# slimme_meter3.net
KiCad netlist of a schematic drawn in EAGLE
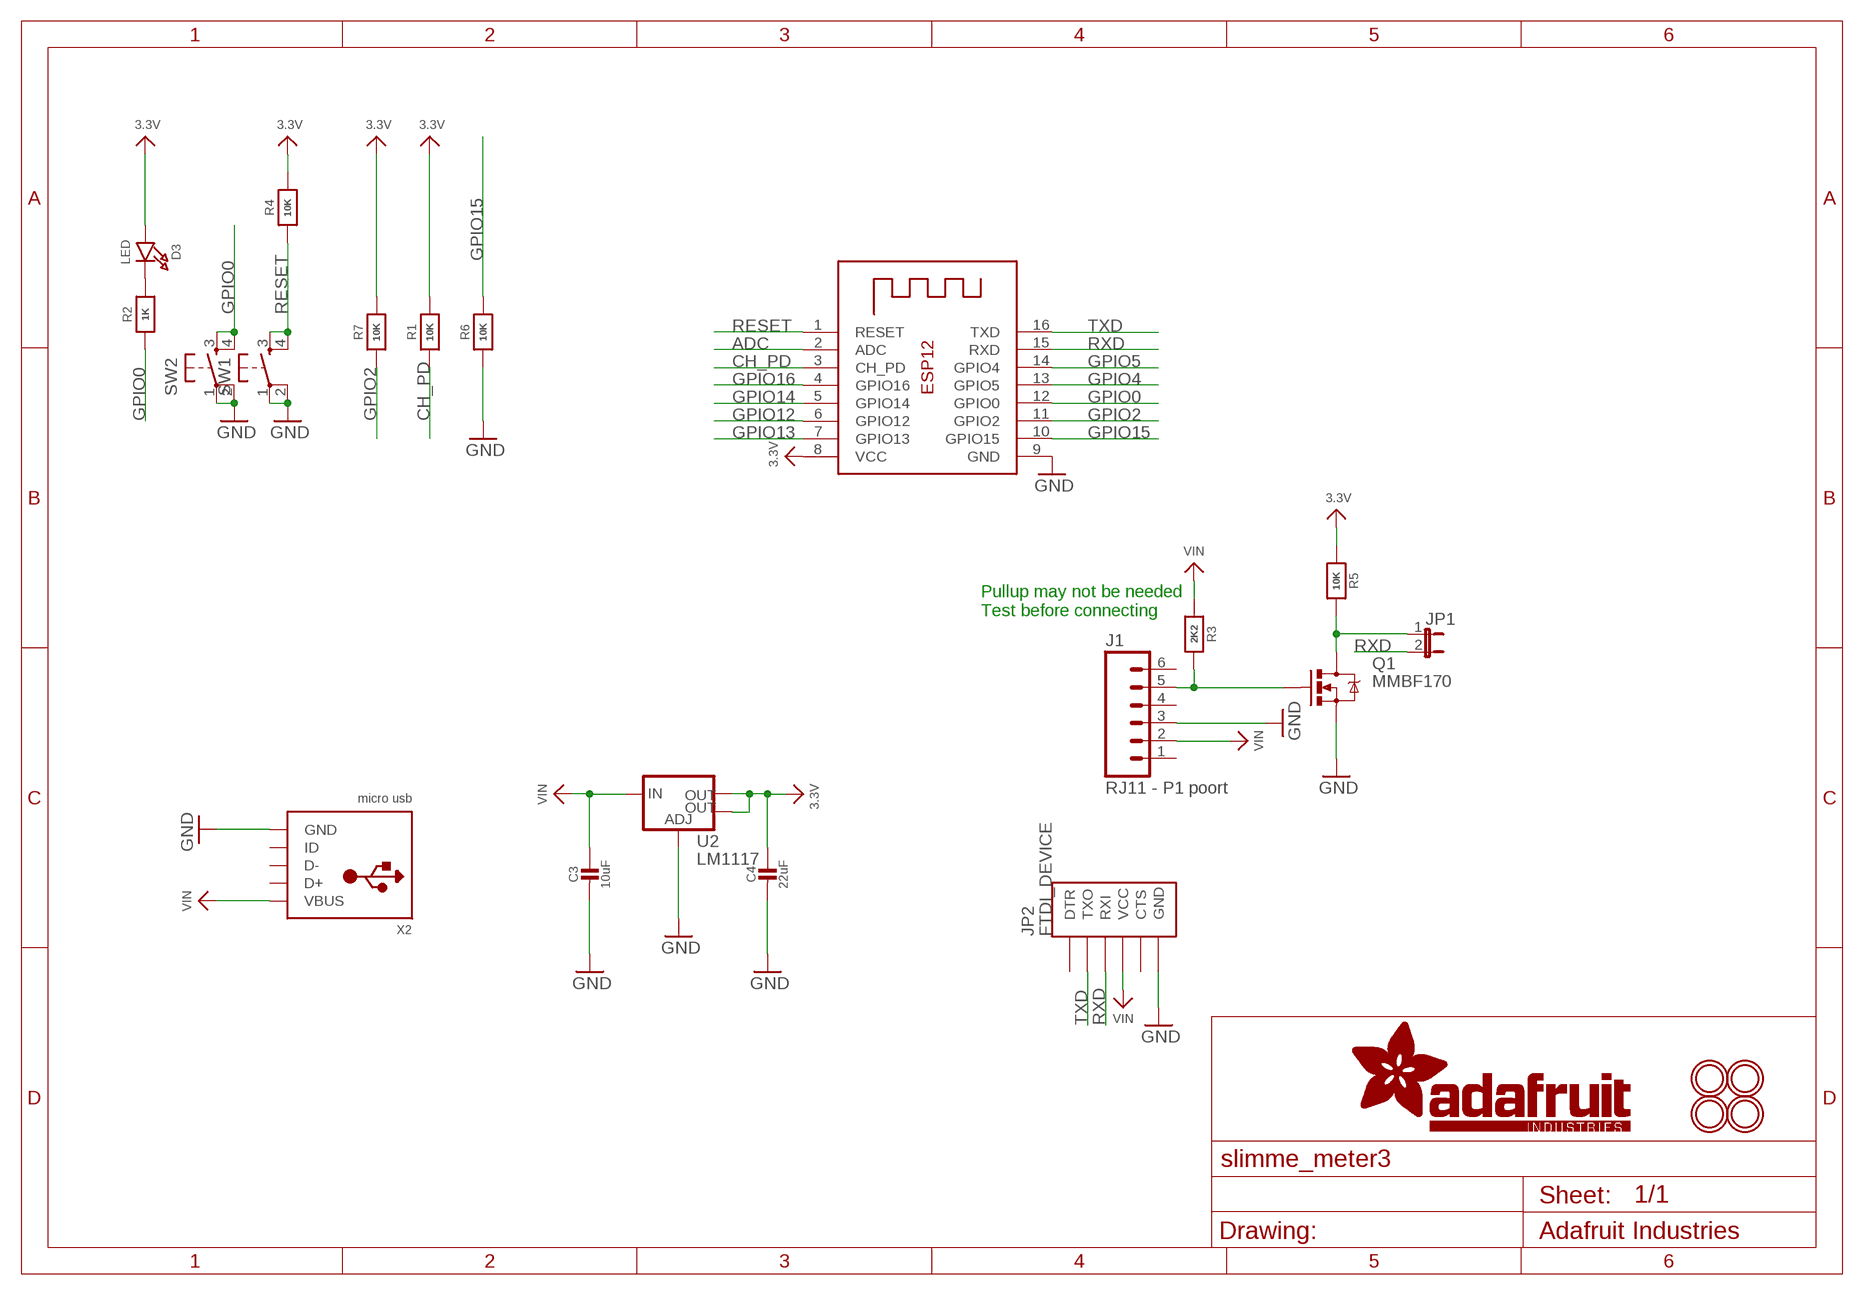
[diagram p0: schematic, sheet 1]

(export (version "E")
  (design (tool "Eeschema 10.0.6"))
  (components
    (comp (ref "C3")
      (value "10uF")
      (footprint "eagle-import:0805-NO")
      (libsource (lib "eagle-import") (part "CAP_CERAMIC0805-NOOUTLINE"))
    )
    (comp (ref "C4")
      (value "22uF")
      (footprint "eagle-import:0805-NO")
      (libsource (lib "eagle-import") (part "CAP_CERAMIC0805-NOOUTLINE"))
    )
    (comp (ref "D3")
      (value "LED")
      (footprint "eagle-import:CHIPLED_0805_NOOUTLINE")
      (libsource (lib "eagle-import") (part "LED0805_NOOUTLINE"))
    )
    (comp (ref "J1")
      (value "RJ11 - P1 poort")
      (footprint "eagle-import:RJ11-6")
      (libsource (lib "eagle-import") (part "RJ11-6PTH"))
    )
    (comp (ref "JP1")
      (value "JUMPER-2PTH")
      (footprint "eagle-import:1X02")
      (libsource (lib "eagle-import") (part "JUMPER-2PTH"))
    )
    (comp (ref "JP2")
      (value "FTDI_DEVICE")
      (footprint "eagle-import:FTDI_DEVICE_SIDE")
      (libsource (lib "eagle-import") (part "FTDI_DEVICE"))
    )
    (comp (ref "Q1")
      (value "MMBF170")
      (footprint "eagle-import:SOT323")
      (libsource (lib "eagle-import") (part "MOSFET-NCHANNEL2N7002PW"))
    )
    (comp (ref "R1")
      (value "10K")
      (footprint "eagle-import:0805-NO")
      (libsource (lib "eagle-import") (part "RESISTOR0805_NOOUTLINE"))
    )
    (comp (ref "R2")
      (value "1K")
      (footprint "eagle-import:0805-NO")
      (libsource (lib "eagle-import") (part "RESISTOR0805_NOOUTLINE"))
    )
    (comp (ref "R3")
      (value "2K2")
      (footprint "eagle-import:0805-NO")
      (libsource (lib "eagle-import") (part "RESISTOR0805_NOOUTLINE"))
    )
    (comp (ref "R4")
      (value "10K")
      (footprint "eagle-import:0805-NO")
      (libsource (lib "eagle-import") (part "RESISTOR0805_NOOUTLINE"))
    )
    (comp (ref "R5")
      (value "10K")
      (footprint "eagle-import:0805-NO")
      (libsource (lib "eagle-import") (part "RESISTOR0805_NOOUTLINE"))
    )
    (comp (ref "R6")
      (value "10K")
      (footprint "eagle-import:0805-NO")
      (libsource (lib "eagle-import") (part "RESISTOR0805_NOOUTLINE"))
    )
    (comp (ref "R7")
      (value "10K")
      (footprint "eagle-import:0805-NO")
      (libsource (lib "eagle-import") (part "RESISTOR0805_NOOUTLINE"))
    )
    (comp (ref "SW1")
      (value "TACTILE-SWITCH-PTH")
      (footprint "eagle-import:TAC-SWITCH-PTH")
      (libsource (lib "eagle-import") (part "TACTILE-SWITCH-PTH"))
    )
    (comp (ref "SW2")
      (value "TACTILE-SWITCH-PTH")
      (footprint "eagle-import:TAC-SWITCH-PTH")
      (libsource (lib "eagle-import") (part "TACTILE-SWITCH-PTH"))
    )
    (comp (ref "U$15")
      (value "MOUNTINGHOLE2.5")
      (footprint "eagle-import:MOUNTINGHOLE_2.5_PLATED")
      (libsource (lib "eagle-import") (part "MOUNTINGHOLE2.5"))
    )
    (comp (ref "U$16")
      (value "MOUNTINGHOLE2.5")
      (footprint "eagle-import:MOUNTINGHOLE_2.5_PLATED")
      (libsource (lib "eagle-import") (part "MOUNTINGHOLE2.5"))
    )
    (comp (ref "U$17")
      (value "MOUNTINGHOLE2.5")
      (footprint "eagle-import:MOUNTINGHOLE_2.5_PLATED")
      (libsource (lib "eagle-import") (part "MOUNTINGHOLE2.5"))
    )
    (comp (ref "U$18")
      (value "MOUNTINGHOLE2.5")
      (footprint "eagle-import:MOUNTINGHOLE_2.5_PLATED")
      (libsource (lib "eagle-import") (part "MOUNTINGHOLE2.5"))
    )
    (comp (ref "U2")
      (value "LM1117")
      (footprint "eagle-import:SOT223")
      (libsource (lib "eagle-import") (part "V_REG_LM1117SOT223"))
    )
    (comp (ref "X1")
      (value "ESP-12")
      (footprint "eagle-import:ESP-12")
      (libsource (lib "eagle-import") (part "ESP-12"))
    )
    (comp (ref "X2")
      (value "micro usb")
      (footprint "eagle-import:4UCONN_20329")
      (libsource (lib "eagle-import") (part "USBMICRO_20329"))
    )
  )
  (nets
    (net (code "1") (name "/ADC") (class "Default")
      (node (ref "X1") (pin "2") (pinfunction "ADC_2") (pintype "passive"))
    )
    (net (code "2") (name "/CH_PD") (class "Default")
      (node (ref "R1") (pin "1") (pinfunction "1_1") (pintype "passive"))
      (node (ref "X1") (pin "3") (pinfunction "CH_PD_3") (pintype "input"))
    )
    (net (code "3") (name "/GPIO0") (class "Default")
      (node (ref "R2") (pin "1") (pinfunction "1_1") (pintype "passive"))
      (node (ref "SW2") (pin "3") (pinfunction "3_3") (pintype "passive"))
      (node (ref "SW2") (pin "4") (pinfunction "4_4") (pintype "passive"))
      (node (ref "X1") (pin "12") (pinfunction "GPIO0_12") (pintype "bidirectional"))
    )
    (net (code "4") (name "/GPIO2") (class "Default")
      (node (ref "R7") (pin "1") (pinfunction "1_1") (pintype "passive"))
      (node (ref "X1") (pin "11") (pinfunction "GPIO2_11") (pintype "bidirectional"))
    )
    (net (code "5") (name "/GPIO4") (class "Default")
      (node (ref "X1") (pin "13") (pinfunction "GPIO5_13") (pintype "bidirectional"))
    )
    (net (code "6") (name "/GPIO5") (class "Default")
      (node (ref "X1") (pin "14") (pinfunction "GPIO4_14") (pintype "bidirectional"))
    )
    (net (code "7") (name "/GPIO12") (class "Default")
      (node (ref "X1") (pin "6") (pinfunction "GPIO12_6") (pintype "bidirectional"))
    )
    (net (code "8") (name "/GPIO13") (class "Default")
      (node (ref "X1") (pin "7") (pinfunction "GPIO13_7") (pintype "bidirectional"))
    )
    (net (code "9") (name "/GPIO14") (class "Default")
      (node (ref "X1") (pin "5") (pinfunction "GPIO14_5") (pintype "bidirectional"))
    )
    (net (code "10") (name "/GPIO15") (class "Default")
      (node (ref "R6") (pin "2") (pinfunction "2_2") (pintype "passive"))
      (node (ref "X1") (pin "10") (pinfunction "GPIO15_10") (pintype "bidirectional"))
    )
    (net (code "11") (name "/GPIO16") (class "Default")
      (node (ref "X1") (pin "4") (pinfunction "GPIO16_4") (pintype "bidirectional"))
    )
    (net (code "12") (name "/RESET") (class "Default")
      (node (ref "R4") (pin "1") (pinfunction "1_1") (pintype "passive"))
      (node (ref "SW1") (pin "3") (pinfunction "3_3") (pintype "passive"))
      (node (ref "SW1") (pin "4") (pinfunction "4_4") (pintype "passive"))
      (node (ref "X1") (pin "1") (pinfunction "RESET_1") (pintype "input"))
    )
    (net (code "13") (name "/RXD") (class "Default")
      (node (ref "JP1") (pin "2") (pinfunction "2_2") (pintype "passive"))
      (node (ref "JP2") (pin "P$3") (pinfunction "RXI_P$3") (pintype "bidirectional"))
      (node (ref "X1") (pin "15") (pinfunction "RXD_15") (pintype "input"))
    )
    (net (code "14") (name "/TXD") (class "Default")
      (node (ref "JP2") (pin "P$2") (pinfunction "TXO_P$2") (pintype "bidirectional"))
      (node (ref "X1") (pin "16") (pinfunction "TXD_16") (pintype "output"))
    )
    (net (code "15") (name "3.3V") (class "Default")
      (node (ref "C4") (pin "1") (pinfunction "1_1") (pintype "passive"))
      (node (ref "D3") (pin "A") (pinfunction "A_A") (pintype "passive"))
      (node (ref "R1") (pin "2") (pinfunction "2_2") (pintype "passive"))
      (node (ref "R4") (pin "2") (pinfunction "2_2") (pintype "passive"))
      (node (ref "R5") (pin "1") (pinfunction "1_1") (pintype "passive"))
      (node (ref "R7") (pin "2") (pinfunction "2_2") (pintype "passive"))
      (node (ref "U2") (pin "2") (pinfunction "OUT_2") (pintype "output"))
      (node (ref "U2") (pin "4") (pinfunction "OUT_4") (pintype "output"))
      (node (ref "X1") (pin "8") (pinfunction "VCC_8") (pintype "power_in"))
    )
    (net (code "16") (name "GND") (class "Default")
      (node (ref "C3") (pin "2") (pinfunction "2_2") (pintype "passive"))
      (node (ref "C4") (pin "2") (pinfunction "2_2") (pintype "passive"))
      (node (ref "J1") (pin "3") (pinfunction "3_3") (pintype "passive"))
      (node (ref "JP2") (pin "P$6") (pinfunction "GND_P$6") (pintype "bidirectional"))
      (node (ref "Q1") (pin "2") (pinfunction "S_2") (pintype "passive"))
      (node (ref "R6") (pin "1") (pinfunction "1_1") (pintype "passive"))
      (node (ref "SW1") (pin "1") (pinfunction "1_1") (pintype "passive"))
      (node (ref "SW1") (pin "2") (pinfunction "2_2") (pintype "passive"))
      (node (ref "SW2") (pin "1") (pinfunction "1_1") (pintype "passive"))
      (node (ref "SW2") (pin "2") (pinfunction "2_2") (pintype "passive"))
      (node (ref "U2") (pin "1") (pinfunction "ADJ_1") (pintype "input"))
      (node (ref "X1") (pin "9") (pinfunction "GND_9") (pintype "power_in"))
      (node (ref "X2") (pin "BASE@1") (pinfunction "GND_BASE@1") (pintype "power_in"))
      (node (ref "X2") (pin "BASE@2") (pinfunction "GND_BASE@2") (pintype "power_in"))
      (node (ref "X2") (pin "GND") (pinfunction "GND_GND") (pintype "power_in"))
      (node (ref "X2") (pin "SPRT@1") (pinfunction "GND_SPRT@1") (pintype "power_in"))
      (node (ref "X2") (pin "SPRT@2") (pinfunction "GND_SPRT@2") (pintype "power_in"))
      (node (ref "X2") (pin "SPRT@3") (pinfunction "GND_SPRT@3") (pintype "power_in"))
      (node (ref "X2") (pin "SPRT@4") (pinfunction "GND_SPRT@4") (pintype "power_in"))
    )
    (net (code "17") (name "Net-(D3-PadC)") (class "Default")
      (node (ref "D3") (pin "C") (pinfunction "C_C") (pintype "passive"))
      (node (ref "R2") (pin "2") (pinfunction "2_2") (pintype "passive"))
    )
    (net (code "18") (name "Net-(Q1-D)") (class "Default")
      (node (ref "JP1") (pin "1") (pinfunction "1_1") (pintype "passive"))
      (node (ref "Q1") (pin "3") (pinfunction "D_3") (pintype "passive"))
      (node (ref "R5") (pin "2") (pinfunction "2_2") (pintype "passive"))
    )
    (net (code "19") (name "Net-(Q1-G)") (class "Default")
      (node (ref "J1") (pin "5") (pinfunction "5_5") (pintype "passive"))
      (node (ref "Q1") (pin "1") (pinfunction "G_1") (pintype "passive"))
      (node (ref "R3") (pin "2") (pinfunction "2_2") (pintype "passive"))
    )
    (net (code "20") (name "VIN") (class "Default")
      (node (ref "C3") (pin "1") (pinfunction "1_1") (pintype "passive"))
      (node (ref "J1") (pin "2") (pinfunction "2_2") (pintype "passive"))
      (node (ref "JP2") (pin "P$4") (pinfunction "VCC_P$4") (pintype "bidirectional"))
      (node (ref "R3") (pin "1") (pinfunction "1_1") (pintype "passive"))
      (node (ref "U2") (pin "3") (pinfunction "IN_3") (pintype "input"))
      (node (ref "X2") (pin "VBUS") (pinfunction "VBUS_VBUS") (pintype "power_in"))
    )
    (net (code "21") (name "unconnected-(J1-Pad1)") (class "Default")
      (node (ref "J1") (pin "1") (pinfunction "1_1") (pintype "passive"))
    )
    (net (code "22") (name "unconnected-(J1-Pad4)") (class "Default")
      (node (ref "J1") (pin "4") (pinfunction "4_4") (pintype "passive"))
    )
    (net (code "23") (name "unconnected-(J1-Pad6)") (class "Default")
      (node (ref "J1") (pin "6") (pinfunction "6_6") (pintype "passive"))
    )
    (net (code "24") (name "unconnected-(JP2-CTS-PadP$5)") (class "Default")
      (node (ref "JP2") (pin "P$5") (pinfunction "CTS_P$5") (pintype "bidirectional"))
    )
    (net (code "25") (name "unconnected-(JP2-DTR-PadP$1)") (class "Default")
      (node (ref "JP2") (pin "P$1") (pinfunction "DTR_P$1") (pintype "bidirectional"))
    )
    (net (code "26") (name "unconnected-(X2-PadD+)") (class "Default")
      (node (ref "X2") (pin "D+") (pinfunction "D+_D+") (pintype "bidirectional"))
    )
    (net (code "27") (name "unconnected-(X2-PadD-)") (class "Default")
      (node (ref "X2") (pin "D-") (pinfunction "D-_D-") (pintype "bidirectional"))
    )
    (net (code "28") (name "unconnected-(X2-PadID)") (class "Default")
      (node (ref "X2") (pin "ID") (pinfunction "ID_ID") (pintype "bidirectional"))
    )
  )
)
